# Controller_Board_Interface.net
KiCad netlist of a schematic drawn in Altium Designer
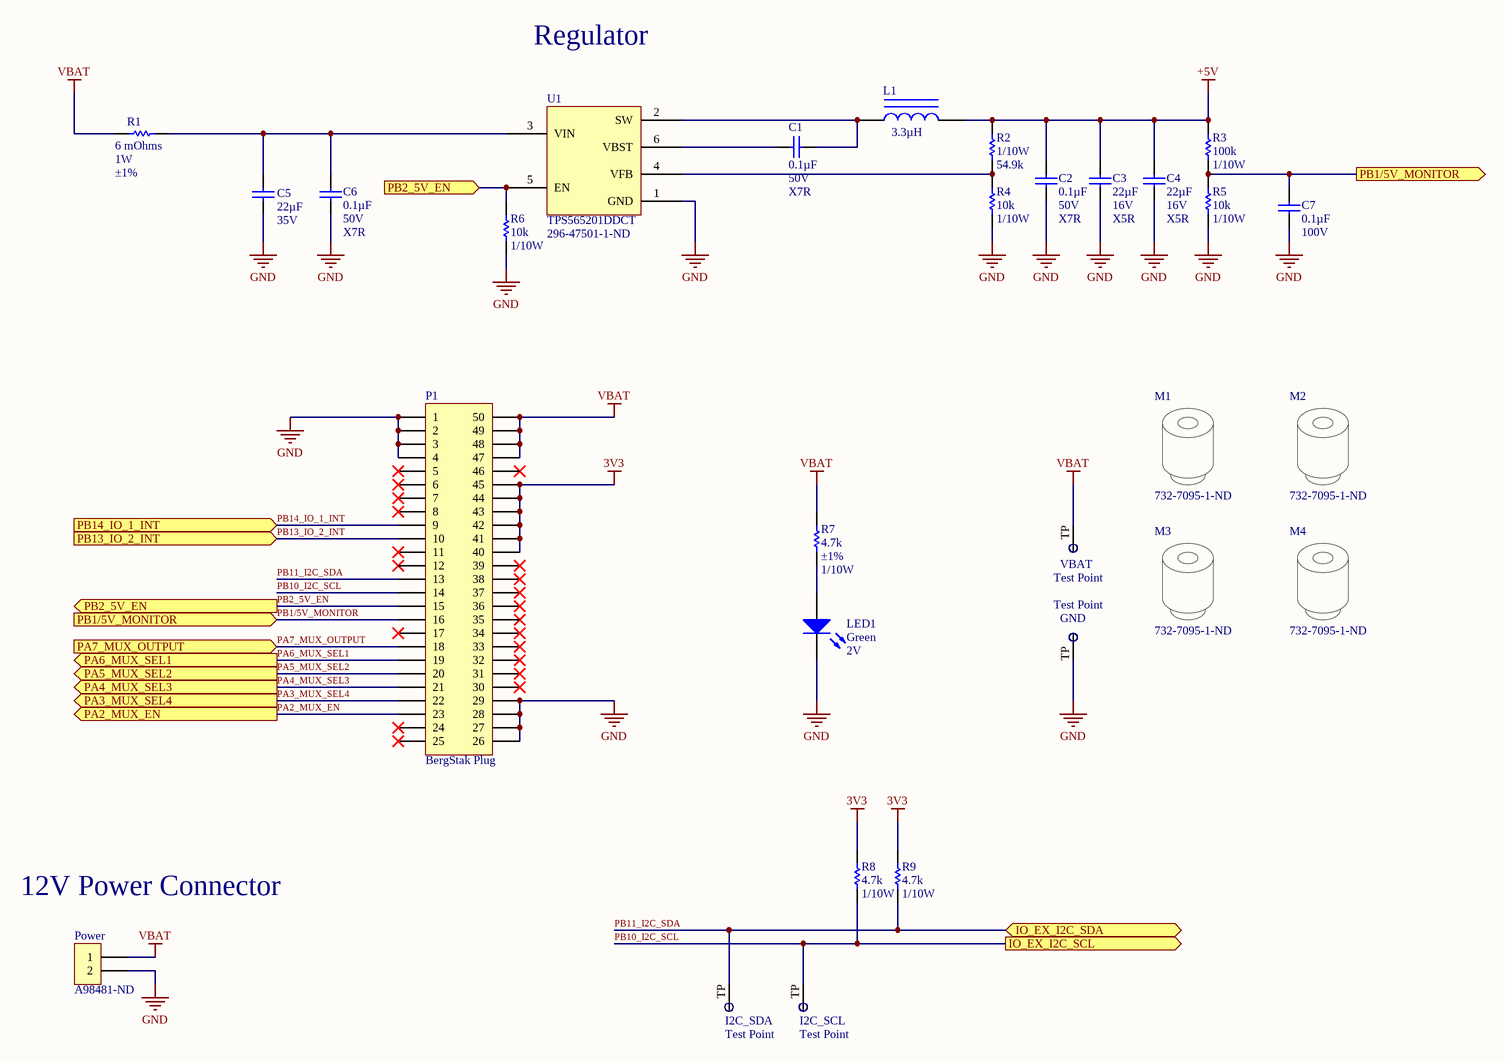
[diagram p0: Controller_Board_Interface.SchDoc]

(export (version "E")
  (design (tool "Eeschema 10.0.6"))
  (components
    (comp (ref "C1")
      (value "CAP CER 0.1UF 50V 10% X7R 0603")
      (footprint "CAP, 0603")
      (description "0.10µF ±10% 50V Ceramic Capacitor X7R 0603 (1608 Metric)")
      (fields
        (field (name "TOLERANCE") "±10%")
        (field (name "CAPACITANCE") "0.1µF")
        (field (name "VOLTAGE") "50V")
        (field (name "TEMPERATURE COEFFICIENT") "X7R")
      )
      (libsource (lib "Schematic Diagrams") (part "CAP CER 0.1UF 50V 10% X7R 0603"))
    )
    (comp (ref "C2")
      (value "CAP CER 0.1UF 50V 10% X7R 0603")
      (footprint "CAP, 0603")
      (description "0.10µF ±10% 50V Ceramic Capacitor X7R 0603 (1608 Metric)")
      (fields
        (field (name "TOLERANCE") "±10%")
        (field (name "CAPACITANCE") "0.1µF")
        (field (name "VOLTAGE") "50V")
        (field (name "TEMPERATURE COEFFICIENT") "X7R")
      )
      (libsource (lib "Schematic Diagrams") (part "CAP CER 0.1UF 50V 10% X7R 0603"))
    )
    (comp (ref "C3")
      (value "CAP CER 22UF 16V ±20% X5R 1210")
      (footprint "CAP, 1210")
      (description "22µF ±20% 16V Ceramic Capacitor X5R 1210 (3225 Metric)")
      (fields
        (field (name "TOLERANCE") "±20%")
        (field (name "CAPACITANCE") "22µF")
        (field (name "VOLTAGE") "16V")
        (field (name "TEMPERATURE COEFFICIENT") "X5R")
      )
      (libsource (lib "Schematic Diagrams") (part "CAP CER 22UF 16V ±20% X5R 1210"))
    )
    (comp (ref "C4")
      (value "CAP CER 22UF 16V ±20% X5R 1210")
      (footprint "CAP, 1210")
      (description "22µF ±20% 16V Ceramic Capacitor X5R 1210 (3225 Metric)")
      (fields
        (field (name "TOLERANCE") "±20%")
        (field (name "CAPACITANCE") "22µF")
        (field (name "VOLTAGE") "16V")
        (field (name "TEMPERATURE COEFFICIENT") "X5R")
      )
      (libsource (lib "Schematic Diagrams") (part "CAP CER 22UF 16V ±20% X5R 1210"))
    )
    (comp (ref "C5")
      (value "CAP CER 22UF 35V X5R 0805")
      (footprint "CAP, 0805")
      (description "22µF ±20% 35V Ceramic Capacitor X5R 0805 (2012 Metric)")
      (fields
        (field (name "MANUFACTURER") "TDK")
        (field (name "MANUFACTURER PART NUMBER") "C2012X5R1V226M125AC")
      )
      (libsource (lib "Schematic Diagrams") (part "CAP CER 22UF 35V X5R 0805"))
    )
    (comp (ref "C6")
      (value "CAP CER 0.1UF 50V 10% X7R 0603")
      (footprint "CAP, 0603")
      (description "0.10µF ±10% 50V Ceramic Capacitor X7R 0603 (1608 Metric)")
      (fields
        (field (name "TOLERANCE") "±10%")
        (field (name "CAPACITANCE") "0.1µF")
        (field (name "VOLTAGE") "50V")
        (field (name "TEMPERATURE COEFFICIENT") "X7R")
      )
      (libsource (lib "Schematic Diagrams") (part "CAP CER 0.1UF 50V 10% X7R 0603"))
    )
    (comp (ref "C7")
      (value "CAP CER 0.1UF 100V 10% X7R 0805")
      (footprint "CAP, 0805")
      (description "0.1µF ±10% 100V Ceramic Capacitor X7R 0805 (2012 Metric)")
      (fields
        (field (name "TOLERANCE") "±10%")
        (field (name "CAPACITANCE") "0.1µF")
        (field (name "VOLTAGE") "100V")
      )
      (libsource (lib "Schematic Diagrams") (part "CAP CER 0.1UF 100V 10% X7R 0805"))
    )
    (comp (ref "GND")
      (value "Test Point")
      (footprint "Test Point")
      (libsource (lib "Schematic Diagrams") (part "Test Point"))
    )
    (comp (ref "I2C_SCL")
      (value "Test Point")
      (footprint "Test Point")
      (libsource (lib "Schematic Diagrams") (part "Test Point"))
    )
    (comp (ref "I2C_SDA")
      (value "Test Point")
      (footprint "Test Point")
      (libsource (lib "Schematic Diagrams") (part "Test Point"))
    )
    (comp (ref "L1")
      (value "FIXED IND 3.3UH 6.5A 25.2 MOHM")
      (footprint "IND_1264EY-3R3N=P3")
      (description "3.3µH Shielded Wirewound Inductor 6.5A 25.2mOhm Max Nonstandard")
      (fields (field (name "INDUCTANCE") "3.3µH") (field (name "TOLERANCE") "±30%"))
      (libsource (lib "Schematic Diagrams") (part "FIXED IND 3.3UH 6.5A 25.2 MOHM"))
    )
    (comp (ref "LED1")
      (value "LED GREEN CLEAR 2V 0603")
      (footprint "LED_0603")
      (description "Green 572nm LED Indication - Discrete 2V 0603 (1608 Metric)")
      (fields
        (field (name "COLOR") "Green")
        (field (name "VOLTAGE - FORWARD (VF) (TYP)") "2V")
        (field (name "MANUFACTURER") "Wurth Electronics Inc.")
        (field (name "MANUFACTURER PART NUMBER") "150060VS75000")
      )
      (libsource (lib "Schematic Diagrams") (part "LED GREEN CLEAR 2V 0603"))
    )
    (comp (ref "M1")
      (value "STANDOFF RND M2.5X0.45 STEEL 5MM")
      (footprint "M2.5 Standoff")
      (fields
        (field (name "MANUFACTURER") "Wurth Electronics")
        (field (name "MANUFACTURER PART NUMBER") "9774050151R")
        (field (name "SUPPLIER PART NUMBER 1") "732-7095-1-ND")
      )
      (libsource (lib "Schematic Diagrams") (part "STANDOFF RND M2.5X0.45 STEEL 5MM"))
    )
    (comp (ref "M2")
      (value "STANDOFF RND M2.5X0.45 STEEL 5MM")
      (footprint "M2.5 Standoff")
      (fields
        (field (name "MANUFACTURER") "Wurth Electronics")
        (field (name "MANUFACTURER PART NUMBER") "9774050151R")
        (field (name "SUPPLIER PART NUMBER 1") "732-7095-1-ND")
      )
      (libsource (lib "Schematic Diagrams") (part "STANDOFF RND M2.5X0.45 STEEL 5MM"))
    )
    (comp (ref "M3")
      (value "STANDOFF RND M2.5X0.45 STEEL 5MM")
      (footprint "M2.5 Standoff")
      (fields
        (field (name "MANUFACTURER") "Wurth Electronics")
        (field (name "MANUFACTURER PART NUMBER") "9774050151R")
        (field (name "SUPPLIER PART NUMBER 1") "732-7095-1-ND")
      )
      (libsource (lib "Schematic Diagrams") (part "STANDOFF RND M2.5X0.45 STEEL 5MM"))
    )
    (comp (ref "M4")
      (value "STANDOFF RND M2.5X0.45 STEEL 5MM")
      (footprint "M2.5 Standoff")
      (fields
        (field (name "MANUFACTURER") "Wurth Electronics")
        (field (name "MANUFACTURER PART NUMBER") "9774050151R")
        (field (name "SUPPLIER PART NUMBER 1") "732-7095-1-ND")
      )
      (libsource (lib "Schematic Diagrams") (part "STANDOFF RND M2.5X0.45 STEEL 5MM"))
    )
    (comp (ref "P1")
      (value "CONN 50POS Bergstak Plug 0.02\"")
      (footprint "CONN, Bergstak 50 Pos Plug")
      (description "50 Position Connector Plug, Outer Shroud Contacts Surface Mount Gold")
      (fields (field (name "SERIES") "BergStak Plug"))
      (libsource (lib "Schematic Diagrams") (part "CONN 50POS Bergstak Plug 0.02{dblquote}"))
    )
    (comp (ref "Power")
      (value "CONN BARRIER STRIP 2CIRC 0.375\"")
      (footprint "6PCV-02-006")
      (description "2 Circuit 0.375\" (9.53mm) Barrier Block Connector, Screws")
      (fields (field (name "SUPPLIER PART NUMBER 1") "A98481-ND"))
      (libsource (lib "Schematic Diagrams") (part "CONN BARRIER STRIP 2CIRC 0.375{dblquote}"))
    )
    (comp (ref "R1")
      (value "RES 0.006 OHM 1% 1W 1206")
      (footprint "RES 1206")
      (description "6 mOhms ±1% 1W Chip Resistor 1206 (3216 Metric) Automotive AEC-Q200, Current Sense Thick Film")
      (fields
        (field (name "RESISTANCE") "6 mOhms")
        (field (name "POWER (WATTS)") "1W")
        (field (name "TOLERANCE") "±1%")
      )
      (libsource (lib "Schematic Diagrams") (part "RES 0.006 OHM 1% 1W 1206"))
    )
    (comp (ref "R2")
      (value "RES 54.9K OHM 1% 1/10W 0603")
      (footprint "RES, 0603")
      (description "54.9k Ohm ±1% 0.1W, 1/10W Chip Resistor 0603 (1608 Metric) Automotive AEC-Q200 Thick Film")
      (fields
        (field (name "MANUFACTURER") "Panasonic Electronic Components")
        (field (name "MANUFACTURER PART NUMBER") "ERJ-3EKF5492V")
        (field (name "POWER (WATTS)") "1/10W")
        (field (name "RESISTANCE (OHMS)") "54.9k")
      )
      (libsource (lib "Schematic Diagrams") (part "RES 54.9K OHM 1% 1/10W 0603"))
    )
    (comp (ref "R3")
      (value "RES 100K OHM 5% 1/8W 0603")
      (footprint "RES, 0603")
      (description "RES SMD 100K OHM 5% 1/10W 0603")
      (fields
        (field (name "TOLERANCE") "±5%")
        (field (name "RESISTANCE") "100k")
        (field (name "POWER") "1/10W")
      )
      (libsource (lib "Schematic Diagrams") (part "RES 100K OHM 5% 1/8W 0603"))
    )
    (comp (ref "R4")
      (value "RES 10K OHM 1% 1/10W 0603")
      (footprint "RES, 0603")
      (description "RES SMD 10K OHM 1% 1/10W 0603")
      (fields
        (field (name "TOLERANCE") "±1%")
        (field (name "RESISTANCE") "10k")
        (field (name "POWER") "1/10W")
      )
      (libsource (lib "Schematic Diagrams") (part "RES 10K OHM 1% 1/10W 0603"))
    )
    (comp (ref "R5")
      (value "RES 10K OHM 1% 1/10W 0603")
      (footprint "RES, 0603")
      (description "RES SMD 10K OHM 1% 1/10W 0603")
      (fields
        (field (name "TOLERANCE") "±1%")
        (field (name "RESISTANCE") "10k")
        (field (name "POWER") "1/10W")
      )
      (libsource (lib "Schematic Diagrams") (part "RES 10K OHM 1% 1/10W 0603"))
    )
    (comp (ref "R6")
      (value "RES 10K OHM 1% 1/10W 0603")
      (footprint "RES, 0603")
      (description "RES SMD 10K OHM 1% 1/10W 0603")
      (fields
        (field (name "TOLERANCE") "±1%")
        (field (name "RESISTANCE") "10k")
        (field (name "POWER") "1/10W")
      )
      (libsource (lib "Schematic Diagrams") (part "RES 10K OHM 1% 1/10W 0603"))
    )
    (comp (ref "R7")
      (value "RES 4.7K OHM 1% 1/10W 0603")
      (footprint "RES, 0603")
      (description "4.7k Ohm ±1% 0.1W, 1/10W Chip Resistor 0603 (1608 Metric) Moisture Resistant Thick Film")
      (fields
        (field (name "RESISTANCE (OHMS)") "4.7k")
        (field (name "TOLERANCE") "±1%")
        (field (name "POWER (WATTS)") "1/10W")
      )
      (libsource (lib "Schematic Diagrams") (part "RES 4.7K OHM 1% 1/10W 0603"))
    )
    (comp (ref "R8")
      (value "RES 4.7K OHM 1% 1/10W 0603")
      (footprint "RES, 0603")
      (description "4.7k Ohm ±1% 0.1W, 1/10W Chip Resistor 0603 (1608 Metric) Moisture Resistant Thick Film")
      (fields
        (field (name "TOLERANCE") "±1%")
        (field (name "RESISTANCE (OHMS)") "4.7k")
        (field (name "POWER (WATTS)") "1/10W")
      )
      (libsource (lib "Schematic Diagrams") (part "RES 4.7K OHM 1% 1/10W 0603"))
    )
    (comp (ref "R9")
      (value "RES 4.7K OHM 1% 1/10W 0603")
      (footprint "RES, 0603")
      (description "4.7k Ohm ±1% 0.1W, 1/10W Chip Resistor 0603 (1608 Metric) Moisture Resistant Thick Film")
      (fields
        (field (name "TOLERANCE") "±1%")
        (field (name "RESISTANCE (OHMS)") "4.7k")
        (field (name "POWER (WATTS)") "1/10W")
      )
      (libsource (lib "Schematic Diagrams") (part "RES 4.7K OHM 1% 1/10W 0603"))
    )
    (comp (ref "U1")
      (value "IC REG BUCK 4.5V TO 17V, 5A, SYNCHRONOUS STE")
      (footprint "IC REG BUCK 4.5V TO 17V, 5A")
      (description "Buck Switching Regulator IC Positive Adjustable 0.6V 1 Output 5A SOT-23-6 Thin, TSOT-23-6")
      (fields
        (field (name "MANUFACTURER") "Texas Instruments")
        (field (name "MANUFACTURER PART NUMBER") "TPS565201DDCT")
        (field (name "SUPPLIER PART NUMBER 1") "296-47501-1-ND")
      )
      (libsource (lib "Schematic Diagrams") (part "IC REG BUCK 4.5V TO 17V, 5A, SYNCHRONOUS STE"))
    )
    (comp (ref "VBAT")
      (value "Test Point")
      (footprint "Test Point")
      (libsource (lib "Schematic Diagrams") (part "Test Point"))
    )
  )
  (nets
    (net (code "1") (name "+5V") (class "Default")
      (node (ref "C2") (pin "1") (pinfunction "1_1") (pintype "passive"))
      (node (ref "C3") (pin "1") (pinfunction "1_1") (pintype "passive"))
      (node (ref "C4") (pin "1") (pinfunction "1_1") (pintype "passive"))
      (node (ref "L1") (pin "2") (pinfunction "2_2") (pintype "passive"))
      (node (ref "R2") (pin "1") (pinfunction "1_1") (pintype "passive"))
      (node (ref "R3") (pin "1") (pinfunction "1_1") (pintype "passive"))
    )
    (net (code "2") (name "/PA2_MUX_EN") (class "Default")
      (node (ref "P1") (pin "23") (pinfunction "23_23") (pintype "passive"))
    )
    (net (code "3") (name "/PA3_MUX_SEL4") (class "Default")
      (node (ref "P1") (pin "22") (pinfunction "22_22") (pintype "passive"))
    )
    (net (code "4") (name "/PA4_MUX_SEL3") (class "Default")
      (node (ref "P1") (pin "21") (pinfunction "21_21") (pintype "passive"))
    )
    (net (code "5") (name "/PA5_MUX_SEL2") (class "Default")
      (node (ref "P1") (pin "20") (pinfunction "20_20") (pintype "passive"))
    )
    (net (code "6") (name "/PA6_MUX_SEL1") (class "Default")
      (node (ref "P1") (pin "19") (pinfunction "19_19") (pintype "passive"))
    )
    (net (code "7") (name "/PA7_MUX_OUTPUT") (class "Default")
      (node (ref "P1") (pin "18") (pinfunction "18_18") (pintype "passive"))
    )
    (net (code "8") (name "/PB1{slash}5V_MONITOR") (class "Default")
      (node (ref "C7") (pin "1") (pinfunction "1_1") (pintype "passive"))
      (node (ref "P1") (pin "16") (pinfunction "16_16") (pintype "passive"))
      (node (ref "R3") (pin "2") (pinfunction "2_2") (pintype "passive"))
      (node (ref "R5") (pin "1") (pinfunction "1_1") (pintype "passive"))
    )
    (net (code "9") (name "/PB2_5V_EN") (class "Default")
      (node (ref "P1") (pin "15") (pinfunction "15_15") (pintype "passive"))
      (node (ref "R6") (pin "1") (pinfunction "1_1") (pintype "passive"))
      (node (ref "U1") (pin "5") (pinfunction "EN_5") (pintype "passive"))
    )
    (net (code "10") (name "/PB10_I2C_SCL") (class "Default")
      (node (ref "I2C_SCL") (pin "TP") (pinfunction "1_TP") (pintype "passive"))
      (node (ref "P1") (pin "14") (pinfunction "14_14") (pintype "passive"))
      (node (ref "R8") (pin "2") (pinfunction "2_2") (pintype "passive"))
    )
    (net (code "11") (name "/PB11_I2C_SDA") (class "Default")
      (node (ref "I2C_SDA") (pin "TP") (pinfunction "1_TP") (pintype "passive"))
      (node (ref "P1") (pin "13") (pinfunction "13_13") (pintype "passive"))
      (node (ref "R9") (pin "2") (pinfunction "2_2") (pintype "passive"))
    )
    (net (code "12") (name "/PB13_IO_2_INT") (class "Default")
      (node (ref "P1") (pin "10") (pinfunction "10_10") (pintype "passive"))
    )
    (net (code "13") (name "/PB14_IO_1_INT") (class "Default")
      (node (ref "P1") (pin "9") (pinfunction "9_9") (pintype "passive"))
    )
    (net (code "14") (name "3V3") (class "Default")
      (node (ref "P1") (pin "40") (pinfunction "40_40") (pintype "passive"))
      (node (ref "P1") (pin "41") (pinfunction "41_41") (pintype "passive"))
      (node (ref "P1") (pin "42") (pinfunction "42_42") (pintype "passive"))
      (node (ref "P1") (pin "43") (pinfunction "43_43") (pintype "passive"))
      (node (ref "P1") (pin "44") (pinfunction "44_44") (pintype "passive"))
      (node (ref "P1") (pin "45") (pinfunction "45_45") (pintype "passive"))
      (node (ref "R8") (pin "1") (pinfunction "1_1") (pintype "passive"))
      (node (ref "R9") (pin "1") (pinfunction "1_1") (pintype "passive"))
    )
    (net (code "15") (name "GND") (class "Default")
      (node (ref "C2") (pin "2") (pinfunction "2_2") (pintype "passive"))
      (node (ref "C3") (pin "2") (pinfunction "2_2") (pintype "passive"))
      (node (ref "C4") (pin "2") (pinfunction "2_2") (pintype "passive"))
      (node (ref "C5") (pin "2") (pinfunction "2_2") (pintype "passive"))
      (node (ref "C6") (pin "2") (pinfunction "2_2") (pintype "passive"))
      (node (ref "C7") (pin "2") (pinfunction "2_2") (pintype "passive"))
      (node (ref "GND") (pin "TP") (pinfunction "1_TP") (pintype "passive"))
      (node (ref "LED1") (pin "2") (pinfunction "K_2") (pintype "passive"))
      (node (ref "P1") (pin "1") (pinfunction "1_1") (pintype "passive"))
      (node (ref "P1") (pin "2") (pinfunction "2_2") (pintype "passive"))
      (node (ref "P1") (pin "26") (pinfunction "26_26") (pintype "passive"))
      (node (ref "P1") (pin "27") (pinfunction "27_27") (pintype "passive"))
      (node (ref "P1") (pin "28") (pinfunction "28_28") (pintype "passive"))
      (node (ref "P1") (pin "29") (pinfunction "29_29") (pintype "passive"))
      (node (ref "P1") (pin "3") (pinfunction "3_3") (pintype "passive"))
      (node (ref "P1") (pin "4") (pinfunction "4_4") (pintype "passive"))
      (node (ref "Power") (pin "2") (pinfunction "2_2") (pintype "passive"))
      (node (ref "R4") (pin "2") (pinfunction "2_2") (pintype "passive"))
      (node (ref "R5") (pin "2") (pinfunction "2_2") (pintype "passive"))
      (node (ref "R6") (pin "2") (pinfunction "2_2") (pintype "passive"))
      (node (ref "U1") (pin "1") (pinfunction "GND_1") (pintype "passive"))
    )
    (net (code "16") (name "Net-(LED1-A)") (class "Default")
      (node (ref "LED1") (pin "1") (pinfunction "A_1") (pintype "passive"))
      (node (ref "R7") (pin "2") (pinfunction "2_2") (pintype "passive"))
    )
    (net (code "17") (name "Net-(U1-SW)") (class "Default")
      (node (ref "C1") (pin "2") (pinfunction "2_2") (pintype "passive"))
      (node (ref "L1") (pin "1") (pinfunction "1_1") (pintype "passive"))
      (node (ref "U1") (pin "2") (pinfunction "SW_2") (pintype "passive"))
    )
    (net (code "18") (name "Net-(U1-VBST)") (class "Default")
      (node (ref "C1") (pin "1") (pinfunction "1_1") (pintype "passive"))
      (node (ref "U1") (pin "6") (pinfunction "VBST_6") (pintype "passive"))
    )
    (net (code "19") (name "Net-(U1-VFB)") (class "Default")
      (node (ref "R2") (pin "2") (pinfunction "2_2") (pintype "passive"))
      (node (ref "R4") (pin "1") (pinfunction "1_1") (pintype "passive"))
      (node (ref "U1") (pin "4") (pinfunction "VFB_4") (pintype "passive"))
    )
    (net (code "20") (name "Net-(U1-VIN)") (class "Default")
      (node (ref "C5") (pin "1") (pinfunction "1_1") (pintype "passive"))
      (node (ref "C6") (pin "1") (pinfunction "1_1") (pintype "passive"))
      (node (ref "R1") (pin "2") (pinfunction "2_2") (pintype "passive"))
      (node (ref "U1") (pin "3") (pinfunction "VIN_3") (pintype "passive"))
    )
    (net (code "21") (name "VBAT") (class "Default")
      (node (ref "P1") (pin "47") (pinfunction "47_47") (pintype "passive"))
      (node (ref "P1") (pin "48") (pinfunction "48_48") (pintype "passive"))
      (node (ref "P1") (pin "49") (pinfunction "49_49") (pintype "passive"))
      (node (ref "P1") (pin "50") (pinfunction "50_50") (pintype "passive"))
      (node (ref "Power") (pin "1") (pinfunction "1_1") (pintype "passive"))
      (node (ref "R1") (pin "1") (pinfunction "1_1") (pintype "passive"))
      (node (ref "R7") (pin "1") (pinfunction "1_1") (pintype "passive"))
      (node (ref "VBAT") (pin "TP") (pinfunction "1_TP") (pintype "passive"))
    )
    (net (code "22") (name "unconnected-(P1-Pad5)") (class "Default")
      (node (ref "P1") (pin "5") (pinfunction "5_5") (pintype "passive+no_connect"))
    )
    (net (code "23") (name "unconnected-(P1-Pad6)") (class "Default")
      (node (ref "P1") (pin "6") (pinfunction "6_6") (pintype "passive+no_connect"))
    )
    (net (code "24") (name "unconnected-(P1-Pad7)") (class "Default")
      (node (ref "P1") (pin "7") (pinfunction "7_7") (pintype "passive+no_connect"))
    )
    (net (code "25") (name "unconnected-(P1-Pad8)") (class "Default")
      (node (ref "P1") (pin "8") (pinfunction "8_8") (pintype "passive+no_connect"))
    )
    (net (code "26") (name "unconnected-(P1-Pad11)") (class "Default")
      (node (ref "P1") (pin "11") (pinfunction "11_11") (pintype "passive+no_connect"))
    )
    (net (code "27") (name "unconnected-(P1-Pad12)") (class "Default")
      (node (ref "P1") (pin "12") (pinfunction "12_12") (pintype "passive+no_connect"))
    )
    (net (code "28") (name "unconnected-(P1-Pad17)") (class "Default")
      (node (ref "P1") (pin "17") (pinfunction "17_17") (pintype "passive+no_connect"))
    )
    (net (code "29") (name "unconnected-(P1-Pad24)") (class "Default")
      (node (ref "P1") (pin "24") (pinfunction "24_24") (pintype "passive+no_connect"))
    )
    (net (code "30") (name "unconnected-(P1-Pad25)") (class "Default")
      (node (ref "P1") (pin "25") (pinfunction "25_25") (pintype "passive+no_connect"))
    )
    (net (code "31") (name "unconnected-(P1-Pad30)") (class "Default")
      (node (ref "P1") (pin "30") (pinfunction "30_30") (pintype "passive+no_connect"))
    )
    (net (code "32") (name "unconnected-(P1-Pad31)") (class "Default")
      (node (ref "P1") (pin "31") (pinfunction "31_31") (pintype "passive+no_connect"))
    )
    (net (code "33") (name "unconnected-(P1-Pad32)") (class "Default")
      (node (ref "P1") (pin "32") (pinfunction "32_32") (pintype "passive+no_connect"))
    )
    (net (code "34") (name "unconnected-(P1-Pad33)") (class "Default")
      (node (ref "P1") (pin "33") (pinfunction "33_33") (pintype "passive+no_connect"))
    )
    (net (code "35") (name "unconnected-(P1-Pad34)") (class "Default")
      (node (ref "P1") (pin "34") (pinfunction "34_34") (pintype "passive+no_connect"))
    )
    (net (code "36") (name "unconnected-(P1-Pad35)") (class "Default")
      (node (ref "P1") (pin "35") (pinfunction "35_35") (pintype "passive+no_connect"))
    )
    (net (code "37") (name "unconnected-(P1-Pad36)") (class "Default")
      (node (ref "P1") (pin "36") (pinfunction "36_36") (pintype "passive+no_connect"))
    )
    (net (code "38") (name "unconnected-(P1-Pad37)") (class "Default")
      (node (ref "P1") (pin "37") (pinfunction "37_37") (pintype "passive+no_connect"))
    )
    (net (code "39") (name "unconnected-(P1-Pad38)") (class "Default")
      (node (ref "P1") (pin "38") (pinfunction "38_38") (pintype "passive+no_connect"))
    )
    (net (code "40") (name "unconnected-(P1-Pad39)") (class "Default")
      (node (ref "P1") (pin "39") (pinfunction "39_39") (pintype "passive+no_connect"))
    )
    (net (code "41") (name "unconnected-(P1-Pad46)") (class "Default")
      (node (ref "P1") (pin "46") (pinfunction "46_46") (pintype "passive+no_connect"))
    )
  )
)
